# M-Pulse_Shield_V2.net
KiCad netlist of a schematic drawn in EAGLE
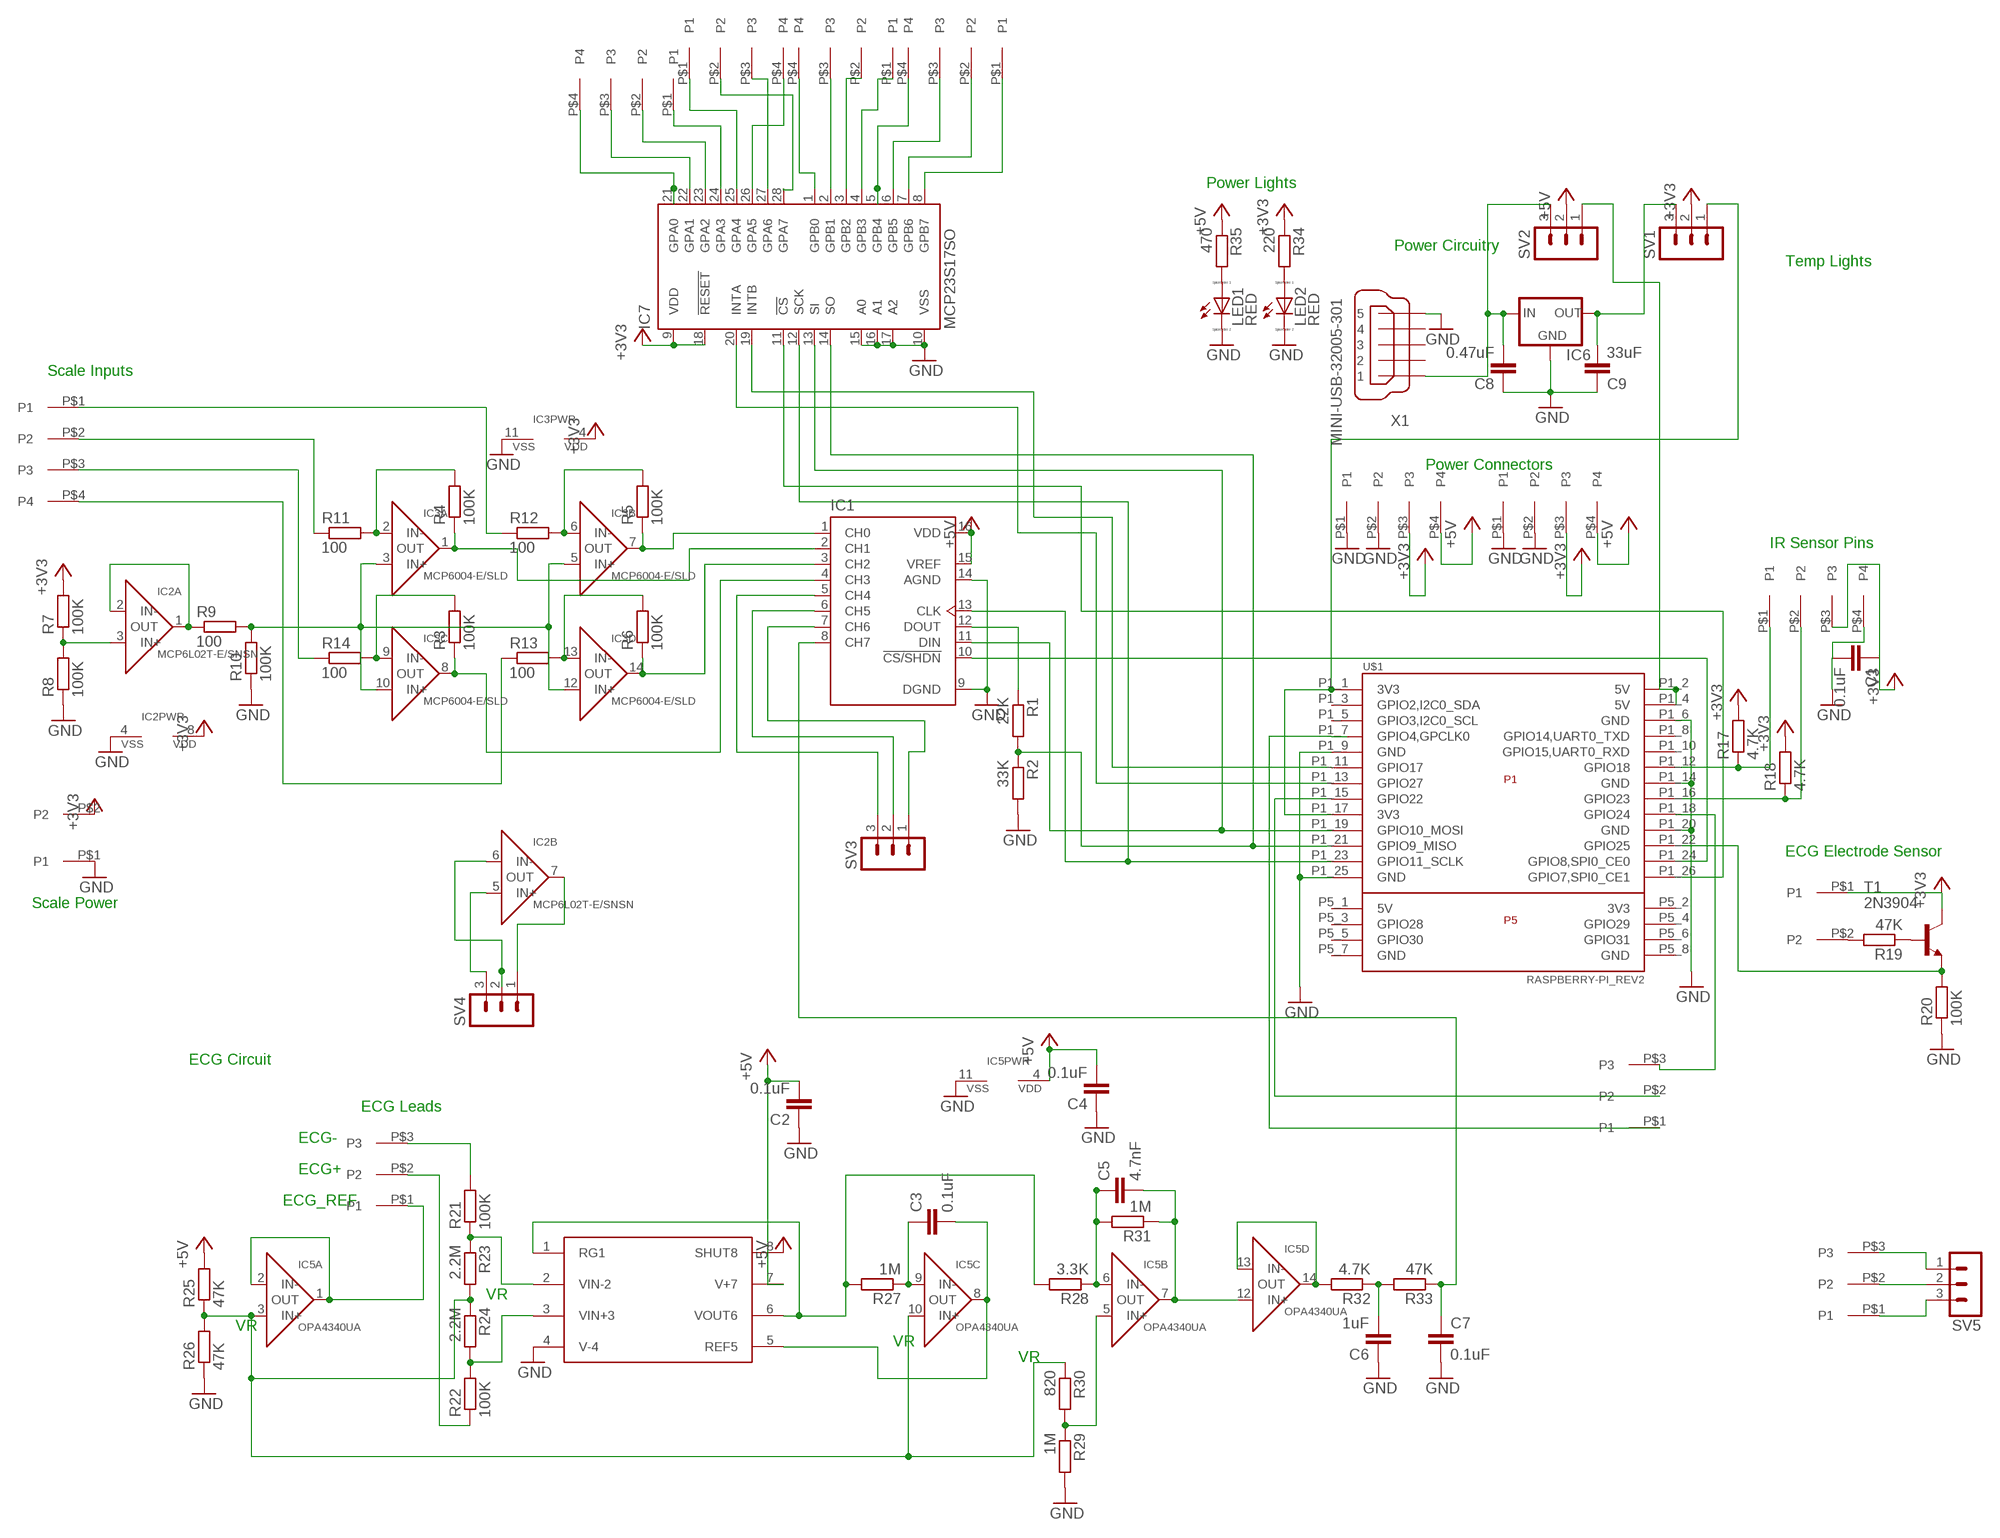
[diagram p0: schematic, sheet 1]

(export (version "E")
  (design (tool "Eeschema 10.0.6"))
  (components
    (comp (ref "C1")
      (value "0.1uF")
      (footprint "eagle-import:C0603")
      (libsource (lib "eagle-import") (part "C-EUC0603"))
    )
    (comp (ref "C2")
      (value "0.1uF")
      (footprint "eagle-import:C0603")
      (libsource (lib "eagle-import") (part "C-EUC0603"))
    )
    (comp (ref "C3")
      (value "0.1uF")
      (footprint "eagle-import:C0603")
      (libsource (lib "eagle-import") (part "C-EUC0603"))
    )
    (comp (ref "C4")
      (value "0.1uF")
      (footprint "eagle-import:C0603")
      (libsource (lib "eagle-import") (part "C-EUC0603"))
    )
    (comp (ref "C5")
      (value "4.7nF")
      (footprint "eagle-import:C0603")
      (libsource (lib "eagle-import") (part "C-EUC0603"))
    )
    (comp (ref "C6")
      (value "1uF")
      (footprint "eagle-import:C0603")
      (libsource (lib "eagle-import") (part "C-EUC0603"))
    )
    (comp (ref "C7")
      (value "0.1uF")
      (footprint "eagle-import:C0603")
      (libsource (lib "eagle-import") (part "C-EUC0603"))
    )
    (comp (ref "C8")
      (value "0.47uF")
      (footprint "eagle-import:C0603")
      (libsource (lib "eagle-import") (part "C-EUC0603"))
    )
    (comp (ref "C9")
      (value "33uF")
      (footprint "eagle-import:C0603")
      (libsource (lib "eagle-import") (part "C-EUC0603"))
    )
    (comp (ref "DIGITALPINS")
      (value "1776275-3")
      (footprint "eagle-import:1776275-3")
      (libsource (lib "eagle-import") (part "1776275-3"))
    )
    (comp (ref "DIGITALPINS1")
      (value "1776275-3")
      (footprint "eagle-import:1776275-3")
      (libsource (lib "eagle-import") (part "1776275-3"))
    )
    (comp (ref "ECG_ES")
      (value "1776275-2")
      (footprint "eagle-import:1776275-2")
      (libsource (lib "eagle-import") (part "1776275-2"))
    )
    (comp (ref "EKGLEADS")
      (value "1776275-3")
      (footprint "eagle-import:1776275-3")
      (libsource (lib "eagle-import") (part "1776275-3"))
    )
    (comp (ref "I/O1")
      (value "1776275-4")
      (footprint "eagle-import:1776275-4")
      (libsource (lib "eagle-import") (part "1776275-4"))
    )
    (comp (ref "I/O2")
      (value "1776275-4")
      (footprint "eagle-import:1776275-4")
      (libsource (lib "eagle-import") (part "1776275-4"))
    )
    (comp (ref "I/O3")
      (value "1776275-4")
      (footprint "eagle-import:1776275-4")
      (libsource (lib "eagle-import") (part "1776275-4"))
    )
    (comp (ref "I/O4")
      (value "1776275-4")
      (footprint "eagle-import:1776275-4")
      (libsource (lib "eagle-import") (part "1776275-4"))
    )
    (comp (ref "IC1")
      (value "MCP3008")
      (footprint "eagle-import:SOIC16N")
      (libsource (lib "eagle-import") (part "MCP3008"))
    )
    (comp (ref "IC2")
      (value "MCP6L02T-E/SNSN")
      (footprint "eagle-import:SO-08")
      (libsource (lib "eagle-import") (part "MCP6L02T-E/SNSN"))
    )
    (comp (ref "IC3")
      (value "MCP6004-E/SLD")
      (footprint "eagle-import:SO14")
      (libsource (lib "eagle-import") (part "MCP6004-E/SLD"))
    )
    (comp (ref "IC4")
      (value "INA321EAVSSOP-8")
      (footprint "eagle-import:VSSOP-8")
      (libsource (lib "eagle-import") (part "INA321EAVSSOP-8"))
    )
    (comp (ref "IC5")
      (value "OPA4340UA")
      (footprint "eagle-import:SO14")
      (libsource (lib "eagle-import") (part "OPA4340UA"))
    )
    (comp (ref "IC6")
      (value "78XXL")
      (footprint "eagle-import:78XXL")
      (libsource (lib "eagle-import") (part "78XXL"))
    )
    (comp (ref "IC7")
      (value "MCP23S17SO")
      (footprint "eagle-import:SO28W")
      (fields (field (name "MF") "MICROCHIP") (field (name "MPN") "MCP23S17-E/SO"))
      (libsource (lib "eagle-import") (part "MCP23S17SO"))
    )
    (comp (ref "IR_I/O")
      (value "1776275-4")
      (footprint "eagle-import:1776275-4")
      (libsource (lib "eagle-import") (part "1776275-4"))
    )
    (comp (ref "LED1")
      (value "RED")
      (footprint "eagle-import:LED_1206")
      (libsource (lib "eagle-import") (part "LED_E"))
    )
    (comp (ref "LED2")
      (value "RED")
      (footprint "eagle-import:LED_1206")
      (libsource (lib "eagle-import") (part "LED_E"))
    )
    (comp (ref "POWEROUT")
      (value "1776275-4")
      (footprint "eagle-import:1776275-4")
      (libsource (lib "eagle-import") (part "1776275-4"))
    )
    (comp (ref "POWEROUT1")
      (value "1776275-4")
      (footprint "eagle-import:1776275-4")
      (libsource (lib "eagle-import") (part "1776275-4"))
    )
    (comp (ref "R1")
      (value "22K")
      (footprint "eagle-import:R0603")
      (libsource (lib "eagle-import") (part "R-EU_R0603"))
    )
    (comp (ref "R2")
      (value "33K")
      (footprint "eagle-import:R0603")
      (libsource (lib "eagle-import") (part "R-EU_R0603"))
    )
    (comp (ref "R3")
      (value "100K")
      (footprint "eagle-import:R0603")
      (libsource (lib "eagle-import") (part "R-EU_R0603"))
    )
    (comp (ref "R4")
      (value "100K")
      (footprint "eagle-import:R0603")
      (libsource (lib "eagle-import") (part "R-EU_R0603"))
    )
    (comp (ref "R5")
      (value "100K")
      (footprint "eagle-import:R0603")
      (libsource (lib "eagle-import") (part "R-EU_R0603"))
    )
    (comp (ref "R6")
      (value "100K")
      (footprint "eagle-import:R0603")
      (libsource (lib "eagle-import") (part "R-EU_R0603"))
    )
    (comp (ref "R7")
      (value "100K")
      (footprint "eagle-import:R0603")
      (libsource (lib "eagle-import") (part "R-EU_R0603"))
    )
    (comp (ref "R8")
      (value "100K")
      (footprint "eagle-import:R0603")
      (libsource (lib "eagle-import") (part "R-EU_R0603"))
    )
    (comp (ref "R9")
      (value "100")
      (footprint "eagle-import:R0603")
      (libsource (lib "eagle-import") (part "R-EU_R0603"))
    )
    (comp (ref "R10")
      (value "100K")
      (footprint "eagle-import:R0603")
      (libsource (lib "eagle-import") (part "R-EU_R0603"))
    )
    (comp (ref "R11")
      (value "100")
      (footprint "eagle-import:R0603")
      (libsource (lib "eagle-import") (part "R-EU_R0603"))
    )
    (comp (ref "R12")
      (value "100")
      (footprint "eagle-import:R0603")
      (libsource (lib "eagle-import") (part "R-EU_R0603"))
    )
    (comp (ref "R13")
      (value "100")
      (footprint "eagle-import:R0603")
      (libsource (lib "eagle-import") (part "R-EU_R0603"))
    )
    (comp (ref "R14")
      (value "100")
      (footprint "eagle-import:R0603")
      (libsource (lib "eagle-import") (part "R-EU_R0603"))
    )
    (comp (ref "R17")
      (value "4.7K")
      (footprint "eagle-import:R0603")
      (libsource (lib "eagle-import") (part "R-EU_R0603"))
    )
    (comp (ref "R18")
      (value "4.7K")
      (footprint "eagle-import:R0603")
      (libsource (lib "eagle-import") (part "R-EU_R0603"))
    )
    (comp (ref "R19")
      (value "47K")
      (footprint "eagle-import:R0603")
      (libsource (lib "eagle-import") (part "R-EU_R0603"))
    )
    (comp (ref "R20")
      (value "100K")
      (footprint "eagle-import:R0603")
      (libsource (lib "eagle-import") (part "R-EU_R0603"))
    )
    (comp (ref "R21")
      (value "100K")
      (footprint "eagle-import:R0603")
      (libsource (lib "eagle-import") (part "R-EU_R0603"))
    )
    (comp (ref "R22")
      (value "100K")
      (footprint "eagle-import:R0603")
      (libsource (lib "eagle-import") (part "R-EU_R0603"))
    )
    (comp (ref "R23")
      (value "2.2M")
      (footprint "eagle-import:R0603")
      (libsource (lib "eagle-import") (part "R-EU_R0603"))
    )
    (comp (ref "R24")
      (value "2.2M")
      (footprint "eagle-import:R0603")
      (libsource (lib "eagle-import") (part "R-EU_R0603"))
    )
    (comp (ref "R25")
      (value "47K")
      (footprint "eagle-import:R0603")
      (libsource (lib "eagle-import") (part "R-EU_R0603"))
    )
    (comp (ref "R26")
      (value "47K")
      (footprint "eagle-import:R0603")
      (libsource (lib "eagle-import") (part "R-EU_R0603"))
    )
    (comp (ref "R27")
      (value "1M")
      (footprint "eagle-import:R0603")
      (libsource (lib "eagle-import") (part "R-EU_R0603"))
    )
    (comp (ref "R28")
      (value "3.3K")
      (footprint "eagle-import:R0603")
      (libsource (lib "eagle-import") (part "R-EU_R0603"))
    )
    (comp (ref "R29")
      (value "1M")
      (footprint "eagle-import:R0603")
      (libsource (lib "eagle-import") (part "R-EU_R0603"))
    )
    (comp (ref "R30")
      (value "820")
      (footprint "eagle-import:R0603")
      (libsource (lib "eagle-import") (part "R-EU_R0603"))
    )
    (comp (ref "R31")
      (value "1M")
      (footprint "eagle-import:R0603")
      (libsource (lib "eagle-import") (part "R-EU_R0603"))
    )
    (comp (ref "R32")
      (value "4.7K")
      (footprint "eagle-import:R0603")
      (libsource (lib "eagle-import") (part "R-EU_R0603"))
    )
    (comp (ref "R33")
      (value "47K")
      (footprint "eagle-import:R0603")
      (libsource (lib "eagle-import") (part "R-EU_R0603"))
    )
    (comp (ref "R34")
      (value "220")
      (footprint "eagle-import:R0603")
      (libsource (lib "eagle-import") (part "R-EU_R0603"))
    )
    (comp (ref "R35")
      (value "470")
      (footprint "eagle-import:R0603")
      (libsource (lib "eagle-import") (part "R-EU_R0603"))
    )
    (comp (ref "SV1")
      (value "MA03-1")
      (footprint "eagle-import:MA03-1")
      (libsource (lib "eagle-import") (part "MA03-1"))
    )
    (comp (ref "SV2")
      (value "MA03-1")
      (footprint "eagle-import:MA03-1")
      (libsource (lib "eagle-import") (part "MA03-1"))
    )
    (comp (ref "SV3")
      (value "MA03-1")
      (footprint "eagle-import:MA03-1")
      (libsource (lib "eagle-import") (part "MA03-1"))
    )
    (comp (ref "SV4")
      (value "MA03-1")
      (footprint "eagle-import:MA03-1")
      (libsource (lib "eagle-import") (part "MA03-1"))
    )
    (comp (ref "SV5")
      (value "MA03-1")
      (footprint "eagle-import:MA03-1")
      (libsource (lib "eagle-import") (part "MA03-1"))
    )
    (comp (ref "S_IN")
      (value "1776275-4")
      (footprint "eagle-import:1776275-4")
      (libsource (lib "eagle-import") (part "1776275-4"))
    )
    (comp (ref "S_PWR")
      (value "1776275-2")
      (footprint "eagle-import:1776275-2")
      (libsource (lib "eagle-import") (part "1776275-2"))
    )
    (comp (ref "T1")
      (value "2N3904")
      (footprint "eagle-import:TO92")
      (libsource (lib "eagle-import") (part "2N3904"))
    )
    (comp (ref "U$1")
      (value "RASPBERRY-PI_REV2")
      (footprint "eagle-import:RASPBERRY-PI_REV2")
      (libsource (lib "eagle-import") (part "RASPBERRY-PI_REV2"))
    )
    (comp (ref "X1")
      (value "MINI-USB-32005-301")
      (footprint "eagle-import:32005-301")
      (libsource (lib "eagle-import") (part "MINI-USB-32005-301"))
    )
  )
  (nets
    (net (code "1") (name "+3V3") (class "Default")
      (node (ref "C1") (pin "1") (pinfunction "1_1") (pintype "passive"))
      (node (ref "ECG_ES") (pin "P$1") (pinfunction "P1_P$1") (pintype "bidirectional"))
      (node (ref "IC2") (pin "8") (pinfunction "VDD_8") (pintype "power_in"))
      (node (ref "IC3") (pin "4") (pinfunction "VDD_4") (pintype "power_in"))
      (node (ref "IC7") (pin "18") (pinfunction "~{RESET}_18") (pintype "input"))
      (node (ref "IC7") (pin "9") (pinfunction "VDD_9") (pintype "power_in"))
      (node (ref "IR_I/O") (pin "P$3") (pinfunction "P3_P$3") (pintype "bidirectional"))
      (node (ref "POWEROUT") (pin "P$3") (pinfunction "P3_P$3") (pintype "bidirectional"))
      (node (ref "POWEROUT1") (pin "P$3") (pinfunction "P3_P$3") (pintype "bidirectional"))
      (node (ref "R17") (pin "2") (pinfunction "2_2") (pintype "passive"))
      (node (ref "R18") (pin "2") (pinfunction "2_2") (pintype "passive"))
      (node (ref "R34") (pin "1") (pinfunction "1_1") (pintype "passive"))
      (node (ref "R7") (pin "2") (pinfunction "2_2") (pintype "passive"))
      (node (ref "SV1") (pin "2") (pinfunction "2_2") (pintype "passive"))
      (node (ref "S_PWR") (pin "P$2") (pinfunction "P2_P$2") (pintype "bidirectional"))
      (node (ref "T1") (pin "1") (pinfunction "C_1") (pintype "passive"))
    )
    (net (code "2") (name "+5V") (class "Default")
      (node (ref "C2") (pin "2") (pinfunction "2_2") (pintype "passive"))
      (node (ref "C4") (pin "2") (pinfunction "2_2") (pintype "passive"))
      (node (ref "IC1") (pin "15") (pinfunction "VREF_15") (pintype "power_in"))
      (node (ref "IC1") (pin "16") (pinfunction "VDD_16") (pintype "power_in"))
      (node (ref "IC4") (pin "7") (pinfunction "V+7_7") (pintype "bidirectional"))
      (node (ref "IC4") (pin "8") (pinfunction "SHUT8_8") (pintype "bidirectional"))
      (node (ref "IC5") (pin "4") (pinfunction "VDD_4") (pintype "power_in"))
      (node (ref "POWEROUT") (pin "P$4") (pinfunction "P4_P$4") (pintype "bidirectional"))
      (node (ref "POWEROUT1") (pin "P$4") (pinfunction "P4_P$4") (pintype "bidirectional"))
      (node (ref "R25") (pin "2") (pinfunction "2_2") (pintype "passive"))
      (node (ref "R35") (pin "1") (pinfunction "1_1") (pintype "passive"))
      (node (ref "SV2") (pin "2") (pinfunction "2_2") (pintype "passive"))
    )
    (net (code "3") (name "GND") (class "Default")
      (node (ref "C1") (pin "2") (pinfunction "2_2") (pintype "passive"))
      (node (ref "C2") (pin "1") (pinfunction "1_1") (pintype "passive"))
      (node (ref "C4") (pin "1") (pinfunction "1_1") (pintype "passive"))
      (node (ref "C6") (pin "1") (pinfunction "1_1") (pintype "passive"))
      (node (ref "C7") (pin "2") (pinfunction "2_2") (pintype "passive"))
      (node (ref "C8") (pin "1") (pinfunction "1_1") (pintype "passive"))
      (node (ref "C9") (pin "1") (pinfunction "1_1") (pintype "passive"))
      (node (ref "IC1") (pin "14") (pinfunction "AGND_14") (pintype "power_in"))
      (node (ref "IC1") (pin "9") (pinfunction "DGND_9") (pintype "power_in"))
      (node (ref "IC2") (pin "4") (pinfunction "VSS_4") (pintype "power_in"))
      (node (ref "IC3") (pin "11") (pinfunction "VSS_11") (pintype "power_in"))
      (node (ref "IC4") (pin "4") (pinfunction "V-4_4") (pintype "bidirectional"))
      (node (ref "IC5") (pin "11") (pinfunction "VSS_11") (pintype "power_in"))
      (node (ref "IC6") (pin "GND") (pinfunction "GND_GND") (pintype "input"))
      (node (ref "IC7") (pin "10") (pinfunction "VSS_10") (pintype "power_in"))
      (node (ref "IC7") (pin "15") (pinfunction "A0_15") (pintype "input"))
      (node (ref "IC7") (pin "16") (pinfunction "A1_16") (pintype "input"))
      (node (ref "IC7") (pin "17") (pinfunction "A2_17") (pintype "input"))
      (node (ref "IR_I/O") (pin "P$4") (pinfunction "P4_P$4") (pintype "bidirectional"))
      (node (ref "LED1") (pin "C") (pinfunction "C_C") (pintype "passive"))
      (node (ref "LED2") (pin "C") (pinfunction "C_C") (pintype "passive"))
      (node (ref "POWEROUT") (pin "P$1") (pinfunction "P1_P$1") (pintype "bidirectional"))
      (node (ref "POWEROUT") (pin "P$2") (pinfunction "P2_P$2") (pintype "bidirectional"))
      (node (ref "POWEROUT1") (pin "P$1") (pinfunction "P1_P$1") (pintype "bidirectional"))
      (node (ref "POWEROUT1") (pin "P$2") (pinfunction "P2_P$2") (pintype "bidirectional"))
      (node (ref "R10") (pin "1") (pinfunction "1_1") (pintype "passive"))
      (node (ref "R2") (pin "2") (pinfunction "2_2") (pintype "passive"))
      (node (ref "R20") (pin "1") (pinfunction "1_1") (pintype "passive"))
      (node (ref "R26") (pin "1") (pinfunction "1_1") (pintype "passive"))
      (node (ref "R29") (pin "2") (pinfunction "2_2") (pintype "passive"))
      (node (ref "R8") (pin "1") (pinfunction "1_1") (pintype "passive"))
      (node (ref "S_PWR") (pin "P$1") (pinfunction "P1_P$1") (pintype "bidirectional"))
      (node (ref "U$1") (pin "P1_14") (pinfunction "GND_P1_14") (pintype "bidirectional"))
      (node (ref "U$1") (pin "P1_20") (pinfunction "GND_P1_20") (pintype "bidirectional"))
      (node (ref "U$1") (pin "P1_25") (pinfunction "GND_P1_25") (pintype "bidirectional"))
      (node (ref "U$1") (pin "P1_6") (pinfunction "GND_P1_6") (pintype "bidirectional"))
      (node (ref "U$1") (pin "P1_9") (pinfunction "GND_P1_9") (pintype "bidirectional"))
      (node (ref "X1") (pin "5") (pinfunction "5_5") (pintype "passive"))
    )
    (net (code "4") (name "Net-(C6-Pad2)") (class "Default")
      (node (ref "C6") (pin "2") (pinfunction "2_2") (pintype "passive"))
      (node (ref "R32") (pin "1") (pinfunction "1_1") (pintype "passive"))
      (node (ref "R33") (pin "2") (pinfunction "2_2") (pintype "passive"))
    )
    (net (code "5") (name "Net-(C8-Pad2)") (class "Default")
      (node (ref "C8") (pin "2") (pinfunction "2_2") (pintype "passive"))
      (node (ref "IC6") (pin "IN") (pinfunction "IN_IN") (pintype "input"))
      (node (ref "SV2") (pin "3") (pinfunction "3_3") (pintype "passive"))
      (node (ref "X1") (pin "1") (pinfunction "1_1") (pintype "passive"))
    )
    (net (code "6") (name "Net-(C9-Pad2)") (class "Default")
      (node (ref "C9") (pin "2") (pinfunction "2_2") (pintype "passive"))
      (node (ref "IC6") (pin "OUT") (pinfunction "OUT_OUT") (pintype "passive"))
      (node (ref "SV1") (pin "3") (pinfunction "3_3") (pintype "passive"))
    )
    (net (code "7") (name "Net-(DIGITALPINS-P1)") (class "Default")
      (node (ref "DIGITALPINS") (pin "P$1") (pinfunction "P1_P$1") (pintype "bidirectional"))
      (node (ref "U$1") (pin "P1_7") (pinfunction "GPIO4,GPCLK0_P1_7") (pintype "bidirectional"))
    )
    (net (code "8") (name "Net-(DIGITALPINS-P2)") (class "Default")
      (node (ref "DIGITALPINS") (pin "P$2") (pinfunction "P2_P$2") (pintype "bidirectional"))
      (node (ref "U$1") (pin "P1_15") (pinfunction "GPIO22_P1_15") (pintype "bidirectional"))
    )
    (net (code "9") (name "Net-(DIGITALPINS-P3)") (class "Default")
      (node (ref "DIGITALPINS") (pin "P$3") (pinfunction "P3_P$3") (pintype "bidirectional"))
      (node (ref "U$1") (pin "P1_18") (pinfunction "GPIO24_P1_18") (pintype "bidirectional"))
    )
    (net (code "10") (name "Net-(DIGITALPINS1-P1)") (class "Default")
      (node (ref "DIGITALPINS1") (pin "P$1") (pinfunction "P1_P$1") (pintype "bidirectional"))
      (node (ref "SV5") (pin "3") (pinfunction "3_3") (pintype "passive"))
    )
    (net (code "11") (name "Net-(DIGITALPINS1-P2)") (class "Default")
      (node (ref "DIGITALPINS1") (pin "P$2") (pinfunction "P2_P$2") (pintype "bidirectional"))
      (node (ref "SV5") (pin "2") (pinfunction "2_2") (pintype "passive"))
    )
    (net (code "12") (name "Net-(DIGITALPINS1-P3)") (class "Default")
      (node (ref "DIGITALPINS1") (pin "P$3") (pinfunction "P3_P$3") (pintype "bidirectional"))
      (node (ref "SV5") (pin "1") (pinfunction "1_1") (pintype "passive"))
    )
    (net (code "13") (name "Net-(ECG_ES-P2)") (class "Default")
      (node (ref "ECG_ES") (pin "P$2") (pinfunction "P2_P$2") (pintype "bidirectional"))
      (node (ref "R19") (pin "2") (pinfunction "2_2") (pintype "passive"))
    )
    (net (code "14") (name "Net-(EKGLEADS-P1)") (class "Default")
      (node (ref "EKGLEADS") (pin "P$1") (pinfunction "P1_P$1") (pintype "bidirectional"))
      (node (ref "IC5") (pin "1") (pinfunction "OUT_1") (pintype "output"))
      (node (ref "IC5") (pin "2") (pinfunction "IN-_2") (pintype "input"))
    )
    (net (code "15") (name "Net-(EKGLEADS-P2)") (class "Default")
      (node (ref "EKGLEADS") (pin "P$2") (pinfunction "P2_P$2") (pintype "bidirectional"))
      (node (ref "R22") (pin "1") (pinfunction "1_1") (pintype "passive"))
    )
    (net (code "16") (name "Net-(EKGLEADS-P3)") (class "Default")
      (node (ref "EKGLEADS") (pin "P$3") (pinfunction "P3_P$3") (pintype "bidirectional"))
      (node (ref "R21") (pin "2") (pinfunction "2_2") (pintype "passive"))
    )
    (net (code "17") (name "Net-(I/O1-P1)") (class "Default")
      (node (ref "I/O1") (pin "P$1") (pinfunction "P1_P$1") (pintype "bidirectional"))
      (node (ref "IC7") (pin "24") (pinfunction "GPA3_24") (pintype "bidirectional"))
    )
    (net (code "18") (name "Net-(I/O1-P2)") (class "Default")
      (node (ref "I/O1") (pin "P$2") (pinfunction "P2_P$2") (pintype "bidirectional"))
      (node (ref "IC7") (pin "23") (pinfunction "GPA2_23") (pintype "bidirectional"))
    )
    (net (code "19") (name "Net-(I/O1-P3)") (class "Default")
      (node (ref "I/O1") (pin "P$3") (pinfunction "P3_P$3") (pintype "bidirectional"))
      (node (ref "IC7") (pin "22") (pinfunction "GPA1_22") (pintype "bidirectional"))
    )
    (net (code "20") (name "Net-(I/O1-P4)") (class "Default")
      (node (ref "I/O1") (pin "P$4") (pinfunction "P4_P$4") (pintype "bidirectional"))
      (node (ref "IC7") (pin "21") (pinfunction "GPA0_21") (pintype "bidirectional"))
    )
    (net (code "21") (name "Net-(I/O2-P1)") (class "Default")
      (node (ref "I/O2") (pin "P$1") (pinfunction "P1_P$1") (pintype "bidirectional"))
      (node (ref "IC7") (pin "25") (pinfunction "GPA4_25") (pintype "bidirectional"))
    )
    (net (code "22") (name "Net-(I/O2-P2)") (class "Default")
      (node (ref "I/O2") (pin "P$2") (pinfunction "P2_P$2") (pintype "bidirectional"))
      (node (ref "IC7") (pin "28") (pinfunction "GPA7_28") (pintype "bidirectional"))
    )
    (net (code "23") (name "Net-(I/O2-P3)") (class "Default")
      (node (ref "I/O2") (pin "P$3") (pinfunction "P3_P$3") (pintype "bidirectional"))
      (node (ref "IC7") (pin "27") (pinfunction "GPA6_27") (pintype "bidirectional"))
    )
    (net (code "24") (name "Net-(I/O2-P4)") (class "Default")
      (node (ref "I/O2") (pin "P$4") (pinfunction "P4_P$4") (pintype "bidirectional"))
      (node (ref "IC7") (pin "26") (pinfunction "GPA5_26") (pintype "bidirectional"))
    )
    (net (code "25") (name "Net-(I/O3-P1)") (class "Default")
      (node (ref "I/O3") (pin "P$1") (pinfunction "P1_P$1") (pintype "bidirectional"))
      (node (ref "IC7") (pin "4") (pinfunction "GPB3_4") (pintype "bidirectional"))
    )
    (net (code "26") (name "Net-(I/O3-P2)") (class "Default")
      (node (ref "I/O3") (pin "P$2") (pinfunction "P2_P$2") (pintype "bidirectional"))
      (node (ref "IC7") (pin "3") (pinfunction "GPB2_3") (pintype "bidirectional"))
    )
    (net (code "27") (name "Net-(I/O3-P3)") (class "Default")
      (node (ref "I/O3") (pin "P$3") (pinfunction "P3_P$3") (pintype "bidirectional"))
      (node (ref "IC7") (pin "2") (pinfunction "GPB1_2") (pintype "bidirectional"))
    )
    (net (code "28") (name "Net-(I/O3-P4)") (class "Default")
      (node (ref "I/O3") (pin "P$4") (pinfunction "P4_P$4") (pintype "bidirectional"))
      (node (ref "IC7") (pin "1") (pinfunction "GPB0_1") (pintype "bidirectional"))
    )
    (net (code "29") (name "Net-(I/O4-P1)") (class "Default")
      (node (ref "I/O4") (pin "P$1") (pinfunction "P1_P$1") (pintype "bidirectional"))
      (node (ref "IC7") (pin "8") (pinfunction "GPB7_8") (pintype "bidirectional"))
    )
    (net (code "30") (name "Net-(I/O4-P2)") (class "Default")
      (node (ref "I/O4") (pin "P$2") (pinfunction "P2_P$2") (pintype "bidirectional"))
      (node (ref "IC7") (pin "7") (pinfunction "GPB6_7") (pintype "bidirectional"))
    )
    (net (code "31") (name "Net-(I/O4-P3)") (class "Default")
      (node (ref "I/O4") (pin "P$3") (pinfunction "P3_P$3") (pintype "bidirectional"))
      (node (ref "IC7") (pin "6") (pinfunction "GPB5_6") (pintype "bidirectional"))
    )
    (net (code "32") (name "Net-(I/O4-P4)") (class "Default")
      (node (ref "I/O4") (pin "P$4") (pinfunction "P4_P$4") (pintype "bidirectional"))
      (node (ref "IC7") (pin "5") (pinfunction "GPB4_5") (pintype "bidirectional"))
    )
    (net (code "33") (name "Net-(IC1-CH0)") (class "Default")
      (node (ref "IC1") (pin "1") (pinfunction "CH0_1") (pintype "input"))
      (node (ref "IC3") (pin "7") (pinfunction "OUT_7") (pintype "output"))
      (node (ref "R5") (pin "1") (pinfunction "1_1") (pintype "passive"))
    )
    (net (code "34") (name "Net-(IC1-CH1)") (class "Default")
      (node (ref "IC1") (pin "2") (pinfunction "CH1_2") (pintype "input"))
      (node (ref "IC3") (pin "1") (pinfunction "OUT_1") (pintype "output"))
      (node (ref "R4") (pin "1") (pinfunction "1_1") (pintype "passive"))
    )
    (net (code "35") (name "Net-(IC1-CH2)") (class "Default")
      (node (ref "IC1") (pin "3") (pinfunction "CH2_3") (pintype "input"))
      (node (ref "IC3") (pin "14") (pinfunction "OUT_14") (pintype "output"))
      (node (ref "R6") (pin "1") (pinfunction "1_1") (pintype "passive"))
    )
    (net (code "36") (name "Net-(IC1-CH3)") (class "Default")
      (node (ref "IC1") (pin "4") (pinfunction "CH3_4") (pintype "input"))
      (node (ref "IC3") (pin "8") (pinfunction "OUT_8") (pintype "output"))
      (node (ref "R3") (pin "1") (pinfunction "1_1") (pintype "passive"))
    )
    (net (code "37") (name "Net-(IC1-CH4)") (class "Default")
      (node (ref "IC1") (pin "5") (pinfunction "CH4_5") (pintype "input"))
      (node (ref "SV3") (pin "3") (pinfunction "3_3") (pintype "passive"))
    )
    (net (code "38") (name "Net-(IC1-CH5)") (class "Default")
      (node (ref "IC1") (pin "6") (pinfunction "CH5_6") (pintype "input"))
      (node (ref "SV3") (pin "2") (pinfunction "2_2") (pintype "passive"))
    )
    (net (code "39") (name "Net-(IC1-CH6)") (class "Default")
      (node (ref "IC1") (pin "7") (pinfunction "CH6_7") (pintype "input"))
      (node (ref "SV3") (pin "1") (pinfunction "1_1") (pintype "passive"))
    )
    (net (code "40") (name "Net-(IC1-CH7)") (class "Default")
      (node (ref "C7") (pin "1") (pinfunction "1_1") (pintype "passive"))
      (node (ref "IC1") (pin "8") (pinfunction "CH7_8") (pintype "input"))
      (node (ref "R33") (pin "1") (pinfunction "1_1") (pintype "passive"))
    )
    (net (code "41") (name "Net-(IC1-CLK)") (class "Default")
      (node (ref "IC1") (pin "13") (pinfunction "CLK_13") (pintype "input"))
      (node (ref "IC7") (pin "12") (pinfunction "SCK_12") (pintype "input"))
      (node (ref "U$1") (pin "P1_23") (pinfunction "GPIO11_SCLK_P1_23") (pintype "bidirectional"))
    )
    (net (code "42") (name "Net-(IC1-DIN)") (class "Default")
      (node (ref "IC1") (pin "11") (pinfunction "DIN_11") (pintype "input"))
      (node (ref "IC7") (pin "13") (pinfunction "SI_13") (pintype "input"))
      (node (ref "U$1") (pin "P1_19") (pinfunction "GPIO10_MOSI_P1_19") (pintype "bidirectional"))
    )
    (net (code "43") (name "Net-(IC1-DOUT)") (class "Default")
      (node (ref "IC1") (pin "12") (pinfunction "DOUT_12") (pintype "output"))
      (node (ref "R1") (pin "1") (pinfunction "1_1") (pintype "passive"))
    )
    (net (code "44") (name "Net-(IC1-~{CS{slash}SHDN})") (class "Default")
      (node (ref "IC1") (pin "10") (pinfunction "~{CS/SHDN}_10") (pintype "input"))
      (node (ref "U$1") (pin "P1_24") (pinfunction "GPIO8,SPI0_CE0_P1_24") (pintype "bidirectional"))
    )
    (net (code "45") (name "Net-(IC2A-IN+)") (class "Default")
      (node (ref "IC2") (pin "3") (pinfunction "IN+_3") (pintype "input"))
      (node (ref "R7") (pin "1") (pinfunction "1_1") (pintype "passive"))
      (node (ref "R8") (pin "2") (pinfunction "2_2") (pintype "passive"))
    )
    (net (code "46") (name "Net-(IC2A-IN-)") (class "Default")
      (node (ref "IC2") (pin "1") (pinfunction "OUT_1") (pintype "output"))
      (node (ref "IC2") (pin "2") (pinfunction "IN-_2") (pintype "input"))
      (node (ref "R9") (pin "1") (pinfunction "1_1") (pintype "passive"))
    )
    (net (code "47") (name "Net-(IC2B-IN+)") (class "Default")
      (node (ref "IC2") (pin "5") (pinfunction "IN+_5") (pintype "input"))
      (node (ref "SV4") (pin "3") (pinfunction "3_3") (pintype "passive"))
    )
    (net (code "48") (name "Net-(IC2B-IN-)") (class "Default")
      (node (ref "IC2") (pin "6") (pinfunction "IN-_6") (pintype "input"))
      (node (ref "SV4") (pin "2") (pinfunction "2_2") (pintype "passive"))
    )
    (net (code "49") (name "Net-(IC2B-OUT)") (class "Default")
      (node (ref "IC2") (pin "7") (pinfunction "OUT_7") (pintype "output"))
      (node (ref "SV4") (pin "1") (pinfunction "1_1") (pintype "passive"))
    )
    (net (code "50") (name "Net-(IC3A-IN+)") (class "Default")
      (node (ref "IC3") (pin "10") (pinfunction "IN+_10") (pintype "input"))
      (node (ref "IC3") (pin "12") (pinfunction "IN+_12") (pintype "input"))
      (node (ref "IC3") (pin "3") (pinfunction "IN+_3") (pintype "input"))
      (node (ref "IC3") (pin "5") (pinfunction "IN+_5") (pintype "input"))
      (node (ref "R10") (pin "2") (pinfunction "2_2") (pintype "passive"))
      (node (ref "R9") (pin "2") (pinfunction "2_2") (pintype "passive"))
    )
    (net (code "51") (name "Net-(IC3A-IN-)") (class "Default")
      (node (ref "IC3") (pin "2") (pinfunction "IN-_2") (pintype "input"))
      (node (ref "R11") (pin "2") (pinfunction "2_2") (pintype "passive"))
      (node (ref "R4") (pin "2") (pinfunction "2_2") (pintype "passive"))
    )
    (net (code "52") (name "Net-(IC3B-IN-)") (class "Default")
      (node (ref "IC3") (pin "6") (pinfunction "IN-_6") (pintype "input"))
      (node (ref "R12") (pin "2") (pinfunction "2_2") (pintype "passive"))
      (node (ref "R5") (pin "2") (pinfunction "2_2") (pintype "passive"))
    )
    (net (code "53") (name "Net-(IC3C-IN-)") (class "Default")
      (node (ref "IC3") (pin "9") (pinfunction "IN-_9") (pintype "input"))
      (node (ref "R14") (pin "2") (pinfunction "2_2") (pintype "passive"))
      (node (ref "R3") (pin "2") (pinfunction "2_2") (pintype "passive"))
    )
    (net (code "54") (name "Net-(IC3D-IN-)") (class "Default")
      (node (ref "IC3") (pin "13") (pinfunction "IN-_13") (pintype "input"))
      (node (ref "R13") (pin "2") (pinfunction "2_2") (pintype "passive"))
      (node (ref "R6") (pin "2") (pinfunction "2_2") (pintype "passive"))
    )
    (net (code "55") (name "Net-(IC4-REF5)") (class "Default")
      (node (ref "C3") (pin "2") (pinfunction "2_2") (pintype "passive"))
      (node (ref "IC4") (pin "5") (pinfunction "REF5_5") (pintype "bidirectional"))
      (node (ref "IC5") (pin "8") (pinfunction "OUT_8") (pintype "output"))
    )
    (net (code "56") (name "Net-(IC4-RG1)") (class "Default")
      (node (ref "IC4") (pin "1") (pinfunction "RG1_1") (pintype "bidirectional"))
      (node (ref "IC4") (pin "6") (pinfunction "VOUT6_6") (pintype "bidirectional"))
      (node (ref "R27") (pin "2") (pinfunction "2_2") (pintype "passive"))
      (node (ref "R28") (pin "2") (pinfunction "2_2") (pintype "passive"))
    )
    (net (code "57") (name "Net-(IC4-VIN+3)") (class "Default")
      (node (ref "IC4") (pin "3") (pinfunction "VIN+3_3") (pintype "bidirectional"))
      (node (ref "R22") (pin "2") (pinfunction "2_2") (pintype "passive"))
      (node (ref "R24") (pin "2") (pinfunction "2_2") (pintype "passive"))
    )
    (net (code "58") (name "Net-(IC4-VIN-2)") (class "Default")
      (node (ref "IC4") (pin "2") (pinfunction "VIN-2_2") (pintype "bidirectional"))
      (node (ref "R21") (pin "1") (pinfunction "1_1") (pintype "passive"))
      (node (ref "R23") (pin "1") (pinfunction "1_1") (pintype "passive"))
    )
    (net (code "59") (name "Net-(IC5A-IN+)") (class "Default")
      (node (ref "IC5") (pin "10") (pinfunction "IN+_10") (pintype "input"))
      (node (ref "IC5") (pin "3") (pinfunction "IN+_3") (pintype "input"))
      (node (ref "R23") (pin "2") (pinfunction "2_2") (pintype "passive"))
      (node (ref "R24") (pin "1") (pinfunction "1_1") (pintype "passive"))
      (node (ref "R25") (pin "1") (pinfunction "1_1") (pintype "passive"))
      (node (ref "R26") (pin "2") (pinfunction "2_2") (pintype "passive"))
      (node (ref "R30") (pin "1") (pinfunction "1_1") (pintype "passive"))
    )
    (net (code "60") (name "Net-(IC5B-IN+)") (class "Default")
      (node (ref "IC5") (pin "5") (pinfunction "IN+_5") (pintype "input"))
      (node (ref "R29") (pin "1") (pinfunction "1_1") (pintype "passive"))
      (node (ref "R30") (pin "2") (pinfunction "2_2") (pintype "passive"))
    )
    (net (code "61") (name "Net-(IC5B-IN-)") (class "Default")
      (node (ref "C5") (pin "1") (pinfunction "1_1") (pintype "passive"))
      (node (ref "IC5") (pin "6") (pinfunction "IN-_6") (pintype "input"))
      (node (ref "R28") (pin "1") (pinfunction "1_1") (pintype "passive"))
      (node (ref "R31") (pin "2") (pinfunction "2_2") (pintype "passive"))
    )
    (net (code "62") (name "Net-(IC5B-OUT)") (class "Default")
      (node (ref "C5") (pin "2") (pinfunction "2_2") (pintype "passive"))
      (node (ref "IC5") (pin "12") (pinfunction "IN+_12") (pintype "input"))
      (node (ref "IC5") (pin "7") (pinfunction "OUT_7") (pintype "output"))
      (node (ref "R31") (pin "1") (pinfunction "1_1") (pintype "passive"))
    )
    (net (code "63") (name "Net-(IC5C-IN-)") (class "Default")
      (node (ref "C3") (pin "1") (pinfunction "1_1") (pintype "passive"))
      (node (ref "IC5") (pin "9") (pinfunction "IN-_9") (pintype "input"))
      (node (ref "R27") (pin "1") (pinfunction "1_1") (pintype "passive"))
    )
    (net (code "64") (name "Net-(IC5D-IN-)") (class "Default")
      (node (ref "IC5") (pin "13") (pinfunction "IN-_13") (pintype "input"))
      (node (ref "IC5") (pin "14") (pinfunction "OUT_14") (pintype "output"))
      (node (ref "R32") (pin "2") (pinfunction "2_2") (pintype "passive"))
    )
    (net (code "65") (name "Net-(IC7-INTA)") (class "Default")
      (node (ref "IC7") (pin "20") (pinfunction "INTA_20") (pintype "output"))
      (node (ref "U$1") (pin "P1_13") (pinfunction "GPIO27_P1_13") (pintype "bidirectional"))
    )
    (net (code "66") (name "Net-(IC7-INTB)") (class "Default")
      (node (ref "IC7") (pin "19") (pinfunction "INTB_19") (pintype "output"))
      (node (ref "U$1") (pin "P1_11") (pinfunction "GPIO17_P1_11") (pintype "bidirectional"))
    )
    (net (code "67") (name "Net-(IC7-SO)") (class "Default")
      (node (ref "IC7") (pin "14") (pinfunction "SO_14") (pintype "output"))
      (node (ref "R1") (pin "2") (pinfunction "2_2") (pintype "passive"))
      (node (ref "R2") (pin "1") (pinfunction "1_1") (pintype "passive"))
      (node (ref "U$1") (pin "P1_21") (pinfunction "GPIO9_MISO_P1_21") (pintype "bidirectional"))
    )
    (net (code "68") (name "Net-(IC7-~{CS})") (class "Default")
      (node (ref "IC7") (pin "11") (pinfunction "~{CS}_11") (pintype "input"))
      (node (ref "U$1") (pin "P1_26") (pinfunction "GPIO7,SPI0_CE1_P1_26") (pintype "bidirectional"))
    )
    (net (code "69") (name "Net-(IR_I/O-P1)") (class "Default")
      (node (ref "IR_I/O") (pin "P$1") (pinfunction "P1_P$1") (pintype "bidirectional"))
      (node (ref "R17") (pin "1") (pinfunction "1_1") (pintype "passive"))
      (node (ref "U$1") (pin "P1_12") (pinfunction "GPIO18_P1_12") (pintype "bidirectional"))
    )
    (net (code "70") (name "Net-(IR_I/O-P2)") (class "Default")
      (node (ref "IR_I/O") (pin "P$2") (pinfunction "P2_P$2") (pintype "bidirectional"))
      (node (ref "R18") (pin "1") (pinfunction "1_1") (pintype "passive"))
      (node (ref "U$1") (pin "P1_16") (pinfunction "GPIO23_P1_16") (pintype "bidirectional"))
    )
    (net (code "71") (name "Net-(LED1-PadA)") (class "Default")
      (node (ref "LED1") (pin "A") (pinfunction "A_A") (pintype "passive"))
      (node (ref "R35") (pin "2") (pinfunction "2_2") (pintype "passive"))
    )
    (net (code "72") (name "Net-(LED2-PadA)") (class "Default")
      (node (ref "LED2") (pin "A") (pinfunction "A_A") (pintype "passive"))
      (node (ref "R34") (pin "2") (pinfunction "2_2") (pintype "passive"))
    )
    (net (code "73") (name "Net-(SV1-Pad1)") (class "Default")
      (node (ref "SV1") (pin "1") (pinfunction "1_1") (pintype "passive"))
      (node (ref "U$1") (pin "P1_1") (pinfunction "3V3_P1_1") (pintype "bidirectional"))
      (node (ref "U$1") (pin "P1_17") (pinfunction "3V3_P1_17") (pintype "bidirectional"))
    )
    (net (code "74") (name "Net-(SV2-Pad1)") (class "Default")
      (node (ref "SV2") (pin "1") (pinfunction "1_1") (pintype "passive"))
      (node (ref "U$1") (pin "P1_2") (pinfunction "5V_P1_2") (pintype "bidirectional"))
      (node (ref "U$1") (pin "P1_4") (pinfunction "5V_P1_4") (pintype "bidirectional"))
    )
    (net (code "75") (name "Net-(S_IN-P1)") (class "Default")
      (node (ref "R12") (pin "1") (pinfunction "1_1") (pintype "passive"))
      (node (ref "S_IN") (pin "P$1") (pinfunction "P1_P$1") (pintype "bidirectional"))
    )
    (net (code "76") (name "Net-(S_IN-P2)") (class "Default")
      (node (ref "R11") (pin "1") (pinfunction "1_1") (pintype "passive"))
      (node (ref "S_IN") (pin "P$2") (pinfunction "P2_P$2") (pintype "bidirectional"))
    )
    (net (code "77") (name "Net-(S_IN-P3)") (class "Default")
      (node (ref "R14") (pin "1") (pinfunction "1_1") (pintype "passive"))
      (node (ref "S_IN") (pin "P$3") (pinfunction "P3_P$3") (pintype "bidirectional"))
    )
    (net (code "78") (name "Net-(S_IN-P4)") (class "Default")
      (node (ref "R13") (pin "1") (pinfunction "1_1") (pintype "passive"))
      (node (ref "S_IN") (pin "P$4") (pinfunction "P4_P$4") (pintype "bidirectional"))
    )
    (net (code "79") (name "Net-(T1-B)") (class "Default")
      (node (ref "R19") (pin "1") (pinfunction "1_1") (pintype "passive"))
      (node (ref "T1") (pin "2") (pinfunction "B_2") (pintype "passive"))
    )
    (net (code "80") (name "Net-(T1-E)") (class "Default")
      (node (ref "R20") (pin "2") (pinfunction "2_2") (pintype "passive"))
      (node (ref "T1") (pin "3") (pinfunction "E_3") (pintype "passive"))
      (node (ref "U$1") (pin "P1_22") (pinfunction "GPIO25_P1_22") (pintype "bidirectional"))
    )
    (net (code "81") (name "unconnected-(U$1-3V3-PadP5_2)") (class "Default")
      (node (ref "U$1") (pin "P5_2") (pinfunction "3V3_P5_2") (pintype "bidirectional"))
    )
    (net (code "82") (name "unconnected-(U$1-5V-PadP5_1)") (class "Default")
      (node (ref "U$1") (pin "P5_1") (pinfunction "5V_P5_1") (pintype "bidirectional"))
    )
    (net (code "83") (name "unconnected-(U$1-GND-PadP5_7)") (class "Default")
      (node (ref "U$1") (pin "P5_7") (pinfunction "GND_P5_7") (pintype "bidirectional"))
    )
    (net (code "84") (name "unconnected-(U$1-GND-PadP5_8)") (class "Default")
      (node (ref "U$1") (pin "P5_8") (pinfunction "GND_P5_8") (pintype "bidirectional"))
    )
    (net (code "85") (name "unconnected-(U$1-GPIO2,I2C0_SDA-PadP1_3)") (class "Default")
      (node (ref "U$1") (pin "P1_3") (pinfunction "GPIO2,I2C0_SDA_P1_3") (pintype "bidirectional"))
    )
    (net (code "86") (name "unconnected-(U$1-GPIO3,I2C0_SCL-PadP1_5)") (class "Default")
      (node (ref "U$1") (pin "P1_5") (pinfunction "GPIO3,I2C0_SCL_P1_5") (pintype "bidirectional"))
    )
    (net (code "87") (name "unconnected-(U$1-GPIO14,UART0_TXD-PadP1_8)") (class "Default")
      (node (ref "U$1") (pin "P1_8") (pinfunction "GPIO14,UART0_TXD_P1_8") (pintype "bidirectional"))
    )
    (net (code "88") (name "unconnected-(U$1-GPIO15,UART0_RXD-PadP1_10)") (class "Default")
      (node (ref "U$1") (pin "P1_10") (pinfunction "GPIO15,UART0_RXD_P1_10") (pintype "bidirectional"))
    )
    (net (code "89") (name "unconnected-(U$1-GPIO28-PadP5_3)") (class "Default")
      (node (ref "U$1") (pin "P5_3") (pinfunction "GPIO28_P5_3") (pintype "bidirectional"))
    )
    (net (code "90") (name "unconnected-(U$1-GPIO29-PadP5_4)") (class "Default")
      (node (ref "U$1") (pin "P5_4") (pinfunction "GPIO29_P5_4") (pintype "bidirectional"))
    )
    (net (code "91") (name "unconnected-(U$1-GPIO30-PadP5_5)") (class "Default")
      (node (ref "U$1") (pin "P5_5") (pinfunction "GPIO30_P5_5") (pintype "bidirectional"))
    )
    (net (code "92") (name "unconnected-(U$1-GPIO31-PadP5_6)") (class "Default")
      (node (ref "U$1") (pin "P5_6") (pinfunction "GPIO31_P5_6") (pintype "bidirectional"))
    )
    (net (code "93") (name "unconnected-(X1-Pad2)") (class "Default")
      (node (ref "X1") (pin "2") (pinfunction "2_2") (pintype "passive"))
    )
    (net (code "94") (name "unconnected-(X1-Pad3)") (class "Default")
      (node (ref "X1") (pin "3") (pinfunction "3_3") (pintype "passive"))
    )
    (net (code "95") (name "unconnected-(X1-Pad4)") (class "Default")
      (node (ref "X1") (pin "4") (pinfunction "4_4") (pintype "passive"))
    )
  )
)
